# NCKH_2020_Dam.net
KiCad netlist of a schematic drawn in Altium Designer
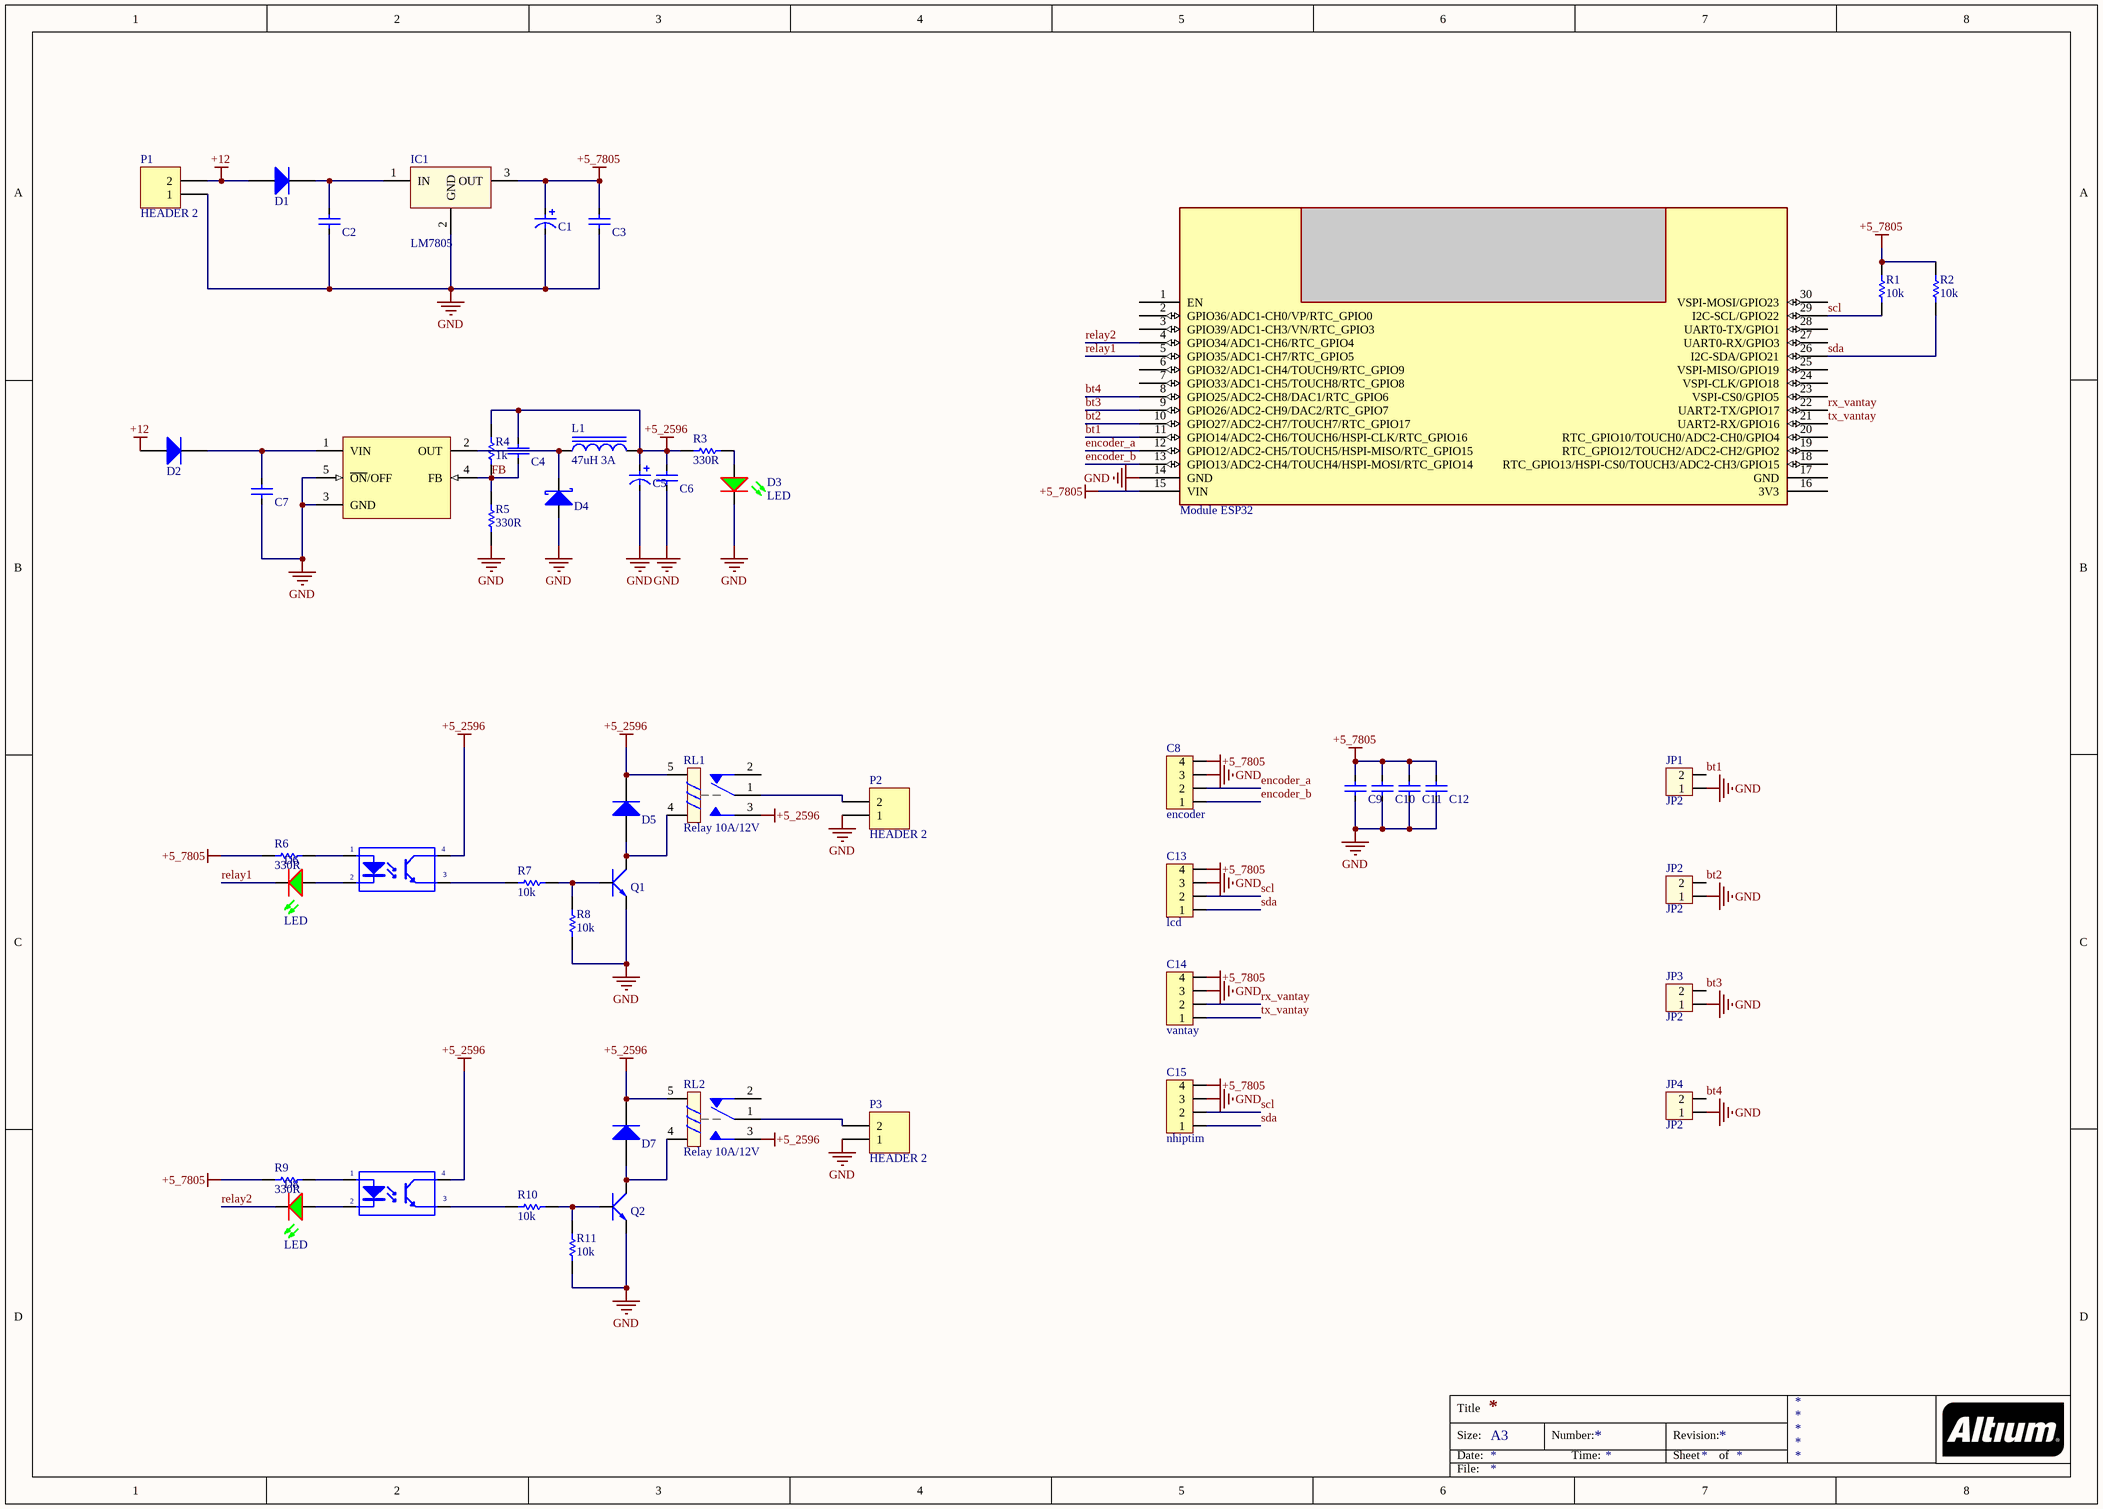
[diagram p0: NCKH 2020_Dam.SchDoc]

(export (version "E")
  (design (tool "Eeschema 10.0.6"))
  (components
    (comp (ref "*1")
      (value "Module ESP32")
      (footprint "Module ESP32")
      (libsource (lib "Lib_NTD_HaUI") (part "Module ESP32"))
    )
    (comp (ref "1") (value "LM2596") (footprint "TO263") (libsource (lib "Lib_NTD_HaUI") (part "LM2596")))
    (comp (ref "C1")
      (value "10uF case A 3216")
      (footprint "CAP TANTALUM A CASE")
      (libsource (lib "Lib_NTD_HaUI") (part "CAP TANTALUM"))
    )
    (comp (ref "C2")
      (value "104")
      (footprint "CAP-0805-SC")
      (libsource (lib "AltiumLibraryTieuBao") (part "CAP-SMDCHIP"))
    )
    (comp (ref "C3")
      (value "104")
      (footprint "CAP-0805-SC")
      (libsource (lib "AltiumLibraryTieuBao") (part "CAP-SMDCHIP"))
    )
    (comp (ref "C4")
      (value "104")
      (footprint "CAP-0805-SC")
      (libsource (lib "AltiumLibraryTieuBao") (part "CAP-SMDCHIP"))
    )
    (comp (ref "C5")
      (value "10uF case A 3216")
      (footprint "CAP TANTALUM A CASE")
      (libsource (lib "Lib_NTD_HaUI") (part "CAP TANTALUM"))
    )
    (comp (ref "C6")
      (value "104")
      (footprint "CAP-0805-SC")
      (libsource (lib "AltiumLibraryTieuBao") (part "CAP-SMDCHIP"))
    )
    (comp (ref "C7")
      (value "104")
      (footprint "CAP-0805-SC")
      (libsource (lib "AltiumLibraryTieuBao") (part "CAP-SMDCHIP"))
    )
    (comp (ref "C8")
      (value "encoder")
      (footprint "Header4")
      (description "Header IDC, 4 x 1 Pin Vertical 2.54mm Pitch (Non-Boxed, Male)")
      (fields
        (field (name "MANUFACTURER") "Würth Elektronik eiSos GmbH")
        (field (name "PARTNO") "613002143121")
        (field (name "CREATED BY") "Karrer Zheng")
      )
      (libsource (lib "LIBRARY") (part "Header4"))
    )
    (comp (ref "C9")
      (value "104")
      (footprint "CAP-0805-SC")
      (libsource (lib "AltiumLibraryTieuBao") (part "CAP-SMDCHIP"))
    )
    (comp (ref "C10")
      (value "104")
      (footprint "CAP-0805-SC")
      (libsource (lib "AltiumLibraryTieuBao") (part "CAP-SMDCHIP"))
    )
    (comp (ref "C11")
      (value "104")
      (footprint "CAP-0805-SC")
      (libsource (lib "AltiumLibraryTieuBao") (part "CAP-SMDCHIP"))
    )
    (comp (ref "C12")
      (value "104")
      (footprint "CAP-0805-SC")
      (libsource (lib "AltiumLibraryTieuBao") (part "CAP-SMDCHIP"))
    )
    (comp (ref "C13")
      (value "lcd")
      (footprint "Header4")
      (description "Header IDC, 4 x 1 Pin Vertical 2.54mm Pitch (Non-Boxed, Male)")
      (fields
        (field (name "MANUFACTURER") "Würth Elektronik eiSos GmbH")
        (field (name "PARTNO") "613002143121")
        (field (name "CREATED BY") "Karrer Zheng")
      )
      (libsource (lib "LIBRARY") (part "Header4"))
    )
    (comp (ref "C14")
      (value "vantay")
      (footprint "Header4")
      (description "Header IDC, 4 x 1 Pin Vertical 2.54mm Pitch (Non-Boxed, Male)")
      (fields
        (field (name "MANUFACTURER") "Würth Elektronik eiSos GmbH")
        (field (name "PARTNO") "613002143121")
        (field (name "CREATED BY") "Karrer Zheng")
      )
      (libsource (lib "LIBRARY") (part "Header4"))
    )
    (comp (ref "C15")
      (value "nhiptim")
      (footprint "Header4")
      (description "Header IDC, 4 x 1 Pin Vertical 2.54mm Pitch (Non-Boxed, Male)")
      (fields
        (field (name "MANUFACTURER") "Würth Elektronik eiSos GmbH")
        (field (name "PARTNO") "613002143121")
        (field (name "CREATED BY") "Karrer Zheng")
      )
      (libsource (lib "LIBRARY") (part "Header4"))
    )
    (comp (ref "D1") (value "M4") (footprint "DO 214AC") (libsource (lib "Lib_NTD_HaUI") (part "DIODE")))
    (comp (ref "D2") (value "M4") (footprint "DO 214AC") (libsource (lib "Lib_NTD_HaUI") (part "DIODE")))
    (comp (ref "D3")
      (value "LED")
      (footprint "LED_SMD_0805")
      (libsource (lib "AltiumLibraryTieuBao") (part "LED"))
    )
    (comp (ref "D4")
      (value "SS34")
      (footprint "DO 214AC")
      (libsource (lib "AltiumLibraryTieuBao") (part "DIODE SCHOTTKY"))
    )
    (comp (ref "D5") (value "M4") (footprint "DO 214AC") (libsource (lib "Lib_NTD_HaUI") (part "DIODE")))
    (comp (ref "D6")
      (value "LED")
      (footprint "LED_SMD_0805")
      (libsource (lib "AltiumLibraryTieuBao") (part "LED"))
    )
    (comp (ref "D7") (value "M4") (footprint "DO 214AC") (libsource (lib "Lib_NTD_HaUI") (part "DIODE")))
    (comp (ref "D8")
      (value "LED")
      (footprint "LED_SMD_0805")
      (libsource (lib "AltiumLibraryTieuBao") (part "LED"))
    )
    (comp (ref "IC1")
      (value "LM7805")
      (footprint "QTO-220H3")
      (description "On ap +, from + 5 to + 24VDC")
      (libsource (lib "syhaunguyen") (part "LM78xx"))
    )
    (comp (ref "JP1")
      (value "JP2")
      (footprint "CON2")
      (description "Connector 2")
      (libsource (lib "syhaunguyen") (part "Con2"))
    )
    (comp (ref "JP2")
      (value "JP2")
      (footprint "CON2")
      (description "Connector 2")
      (libsource (lib "syhaunguyen") (part "Con2"))
    )
    (comp (ref "JP3")
      (value "JP2")
      (footprint "CON2")
      (description "Connector 2")
      (libsource (lib "syhaunguyen") (part "Con2"))
    )
    (comp (ref "JP4")
      (value "JP2")
      (footprint "CON2")
      (description "Connector 2")
      (libsource (lib "syhaunguyen") (part "Con2"))
    )
    (comp (ref "L1")
      (value "47uH 3A")
      (footprint "INDUCTOR SMD 3A")
      (libsource (lib "AltiumLibraryTieuBao") (part "INDUCTOR"))
    )
    (comp (ref "P1")
      (value "HEADER 2")
      (footprint "KF7.62")
      (libsource (lib "AltiumLibraryTieuBao") (part "HEADER 2"))
    )
    (comp (ref "P2") (value "HEADER 2") (footprint "KF7.62") (libsource (lib "") (part "HEADER 2_1")))
    (comp (ref "P3") (value "HEADER 2") (footprint "KF7.62") (libsource (lib "") (part "HEADER 2_1")))
    (comp (ref "Q1") (value "C1815") (footprint "SOT23") (libsource (lib "Lib_NTD_HaUI") (part "C1815")))
    (comp (ref "Q2") (value "C1815") (footprint "SOT23") (libsource (lib "Lib_NTD_HaUI") (part "C1815")))
    (comp (ref "R1")
      (value "10k")
      (footprint "RES-0805-SC")
      (libsource (lib "AltiumLibraryTieuBao") (part "RES"))
    )
    (comp (ref "R2")
      (value "10k")
      (footprint "RES-0805-SC")
      (libsource (lib "AltiumLibraryTieuBao") (part "RES"))
    )
    (comp (ref "R3")
      (value "330R")
      (footprint "RES-0805-SC")
      (libsource (lib "AltiumLibraryTieuBao") (part "RES"))
    )
    (comp (ref "R4")
      (value "1k")
      (footprint "RES-0805-SC")
      (libsource (lib "AltiumLibraryTieuBao") (part "RES"))
    )
    (comp (ref "R5")
      (value "330R")
      (footprint "RES-0805-SC")
      (libsource (lib "AltiumLibraryTieuBao") (part "RES"))
    )
    (comp (ref "R6")
      (value "330R")
      (footprint "RES-0805-SC")
      (libsource (lib "AltiumLibraryTieuBao") (part "RES"))
    )
    (comp (ref "R7")
      (value "10k")
      (footprint "RES-0805-SC")
      (libsource (lib "AltiumLibraryTieuBao") (part "RES"))
    )
    (comp (ref "R8")
      (value "10k")
      (footprint "RES-0805-SC")
      (libsource (lib "AltiumLibraryTieuBao") (part "RES"))
    )
    (comp (ref "R9")
      (value "330R")
      (footprint "RES-0805-SC")
      (libsource (lib "AltiumLibraryTieuBao") (part "RES"))
    )
    (comp (ref "R10")
      (value "10k")
      (footprint "RES-0805-SC")
      (libsource (lib "AltiumLibraryTieuBao") (part "RES"))
    )
    (comp (ref "R11")
      (value "10k")
      (footprint "RES-0805-SC")
      (libsource (lib "AltiumLibraryTieuBao") (part "RES"))
    )
    (comp (ref "RL1")
      (value "Relay 10A/12V")
      (footprint "RL_SPDT_10A")
      (description "Relay SPDT,10A - 12VDC 5 Pin")
      (libsource (lib "syhaunguyen") (part "Relay 1"))
    )
    (comp (ref "RL2")
      (value "Relay 10A/12V")
      (footprint "RL_SPDT_10A")
      (description "Relay SPDT,10A - 12VDC 5 Pin")
      (libsource (lib "syhaunguyen") (part "Relay 1"))
    )
    (comp (ref "U1") (value "PC817") (footprint "PC817") (libsource (lib "Lib_NTD_HaUI") (part "PC817")))
    (comp (ref "U2") (value "PC817") (footprint "PC817") (libsource (lib "Lib_NTD_HaUI") (part "PC817")))
  )
  (nets
    (net (code "1") (name "+5_2596") (class "Default")
      (node (ref "C4") (pin "1") (pinfunction "1_1") (pintype "passive"))
      (node (ref "C5") (pin "1") (pinfunction "1_1") (pintype "passive"))
      (node (ref "C6") (pin "1") (pinfunction "1_1") (pintype "passive"))
      (node (ref "D5") (pin "2") (pinfunction "K_2") (pintype "passive"))
      (node (ref "D7") (pin "2") (pinfunction "K_2") (pintype "passive"))
      (node (ref "L1") (pin "2") (pinfunction "2_2") (pintype "passive"))
      (node (ref "R3") (pin "2") (pinfunction "2_2") (pintype "passive"))
      (node (ref "R4") (pin "2") (pinfunction "2_2") (pintype "passive"))
      (node (ref "RL1") (pin "3") (pinfunction "3_3") (pintype "passive"))
      (node (ref "RL1") (pin "5") (pinfunction "5_5") (pintype "passive"))
      (node (ref "RL2") (pin "3") (pinfunction "3_3") (pintype "passive"))
      (node (ref "RL2") (pin "5") (pinfunction "5_5") (pintype "passive"))
      (node (ref "U1") (pin "4") (pinfunction "C_4") (pintype "passive"))
      (node (ref "U2") (pin "4") (pinfunction "C_4") (pintype "passive"))
    )
    (net (code "2") (name "+5_7805") (class "Default")
      (node (ref "*1") (pin "15") (pinfunction "VIN_15") (pintype "power_in"))
      (node (ref "C1") (pin "1") (pinfunction "1_1") (pintype "passive"))
      (node (ref "C10") (pin "1") (pinfunction "1_1") (pintype "passive"))
      (node (ref "C11") (pin "1") (pinfunction "1_1") (pintype "passive"))
      (node (ref "C12") (pin "1") (pinfunction "1_1") (pintype "passive"))
      (node (ref "C13") (pin "4") (pinfunction "4_4") (pintype "passive"))
      (node (ref "C14") (pin "4") (pinfunction "4_4") (pintype "passive"))
      (node (ref "C15") (pin "4") (pinfunction "4_4") (pintype "passive"))
      (node (ref "C3") (pin "1") (pinfunction "1_1") (pintype "passive"))
      (node (ref "C8") (pin "4") (pinfunction "4_4") (pintype "passive"))
      (node (ref "C9") (pin "1") (pinfunction "1_1") (pintype "passive"))
      (node (ref "IC1") (pin "3") (pinfunction "OUT_3") (pintype "passive"))
      (node (ref "R1") (pin "2") (pinfunction "2_2") (pintype "passive"))
      (node (ref "R2") (pin "2") (pinfunction "2_2") (pintype "passive"))
      (node (ref "R6") (pin "2") (pinfunction "2_2") (pintype "passive"))
      (node (ref "R9") (pin "2") (pinfunction "2_2") (pintype "passive"))
    )
    (net (code "3") (name "+12") (class "Default")
      (node (ref "D1") (pin "1") (pinfunction "A_1") (pintype "passive"))
      (node (ref "D2") (pin "1") (pinfunction "A_1") (pintype "passive"))
      (node (ref "P1") (pin "2") (pinfunction "2_2") (pintype "passive"))
    )
    (net (code "4") (name "/FB") (class "Default")
      (node (ref "1") (pin "4") (pinfunction "FB_4") (pintype "input"))
      (node (ref "C4") (pin "2") (pinfunction "2_2") (pintype "passive"))
      (node (ref "R4") (pin "1") (pinfunction "1_1") (pintype "passive"))
      (node (ref "R5") (pin "2") (pinfunction "2_2") (pintype "passive"))
    )
    (net (code "5") (name "/bt1") (class "Default")
      (node (ref "*1") (pin "11") (pinfunction "GPIO14/ADC2-CH6/TOUCH6/HSPI-CLK/RTC_GPIO16_11") (pintype "bidirectional"))
      (node (ref "JP1") (pin "2") (pinfunction "2_2") (pintype "passive"))
    )
    (net (code "6") (name "/bt2") (class "Default")
      (node (ref "*1") (pin "10") (pinfunction "GPIO27/ADC2-CH7/TOUCH7/RTC_GPIO17_10") (pintype "bidirectional"))
      (node (ref "JP2") (pin "2") (pinfunction "2_2") (pintype "passive"))
    )
    (net (code "7") (name "/bt3") (class "Default")
      (node (ref "*1") (pin "9") (pinfunction "GPIO26/ADC2-CH9/DAC2/RTC_GPIO7_9") (pintype "bidirectional"))
      (node (ref "JP3") (pin "2") (pinfunction "2_2") (pintype "passive"))
    )
    (net (code "8") (name "/bt4") (class "Default")
      (node (ref "*1") (pin "8") (pinfunction "GPIO25/ADC2-CH8/DAC1/RTC_GPIO6_8") (pintype "bidirectional"))
      (node (ref "JP4") (pin "2") (pinfunction "2_2") (pintype "passive"))
    )
    (net (code "9") (name "/encoder_a") (class "Default")
      (node (ref "*1") (pin "12") (pinfunction "GPIO12/ADC2-CH5/TOUCH5/HSPI-MISO/RTC_GPIO15_12") (pintype "bidirectional"))
      (node (ref "C8") (pin "2") (pinfunction "2_2") (pintype "passive"))
    )
    (net (code "10") (name "/encoder_b") (class "Default")
      (node (ref "*1") (pin "13") (pinfunction "GPIO13/ADC2-CH4/TOUCH4/HSPI-MOSI/RTC_GPIO14_13") (pintype "bidirectional"))
      (node (ref "C8") (pin "1") (pinfunction "1_1") (pintype "passive"))
    )
    (net (code "11") (name "/relay1") (class "Default")
      (node (ref "*1") (pin "5") (pinfunction "GPIO35/ADC1-CH7/RTC_GPIO5_5") (pintype "bidirectional"))
      (node (ref "D6") (pin "2") (pinfunction "K_2") (pintype "passive"))
    )
    (net (code "12") (name "/relay2") (class "Default")
      (node (ref "*1") (pin "4") (pinfunction "GPIO34/ADC1-CH6/RTC_GPIO4_4") (pintype "bidirectional"))
      (node (ref "D8") (pin "2") (pinfunction "K_2") (pintype "passive"))
    )
    (net (code "13") (name "/rx_vantay") (class "Default")
      (node (ref "*1") (pin "22") (pinfunction "UART2-TX/GPIO17_22") (pintype "bidirectional"))
      (node (ref "C14") (pin "2") (pinfunction "2_2") (pintype "passive"))
    )
    (net (code "14") (name "/scl") (class "Default")
      (node (ref "*1") (pin "29") (pinfunction "I2C-SCL/GPIO22_29") (pintype "bidirectional"))
      (node (ref "C13") (pin "2") (pinfunction "2_2") (pintype "passive"))
      (node (ref "C15") (pin "2") (pinfunction "2_2") (pintype "passive"))
      (node (ref "R1") (pin "1") (pinfunction "1_1") (pintype "passive"))
    )
    (net (code "15") (name "/sda") (class "Default")
      (node (ref "*1") (pin "26") (pinfunction "I2C-SDA/GPIO21_26") (pintype "bidirectional"))
      (node (ref "C13") (pin "1") (pinfunction "1_1") (pintype "passive"))
      (node (ref "C15") (pin "1") (pinfunction "1_1") (pintype "passive"))
      (node (ref "R2") (pin "1") (pinfunction "1_1") (pintype "passive"))
    )
    (net (code "16") (name "/tx_vantay") (class "Default")
      (node (ref "*1") (pin "21") (pinfunction "UART2-RX/GPIO16_21") (pintype "bidirectional"))
      (node (ref "C14") (pin "1") (pinfunction "1_1") (pintype "passive"))
    )
    (net (code "17") (name "GND") (class "Default")
      (node (ref "*1") (pin "14") (pinfunction "GND_14") (pintype "power_in"))
      (node (ref "1") (pin "3") (pinfunction "GND_3") (pintype "power_in"))
      (node (ref "1") (pin "5") (pinfunction "~{ON}/OFF_5") (pintype "input"))
      (node (ref "C1") (pin "2") (pinfunction "2_2") (pintype "passive"))
      (node (ref "C10") (pin "2") (pinfunction "2_2") (pintype "passive"))
      (node (ref "C11") (pin "2") (pinfunction "2_2") (pintype "passive"))
      (node (ref "C12") (pin "2") (pinfunction "2_2") (pintype "passive"))
      (node (ref "C13") (pin "3") (pinfunction "3_3") (pintype "passive"))
      (node (ref "C14") (pin "3") (pinfunction "3_3") (pintype "passive"))
      (node (ref "C15") (pin "3") (pinfunction "3_3") (pintype "passive"))
      (node (ref "C2") (pin "2") (pinfunction "2_2") (pintype "passive"))
      (node (ref "C3") (pin "2") (pinfunction "2_2") (pintype "passive"))
      (node (ref "C5") (pin "2") (pinfunction "2_2") (pintype "passive"))
      (node (ref "C6") (pin "2") (pinfunction "2_2") (pintype "passive"))
      (node (ref "C7") (pin "2") (pinfunction "2_2") (pintype "passive"))
      (node (ref "C8") (pin "3") (pinfunction "3_3") (pintype "passive"))
      (node (ref "C9") (pin "2") (pinfunction "2_2") (pintype "passive"))
      (node (ref "D3") (pin "2") (pinfunction "K_2") (pintype "passive"))
      (node (ref "D4") (pin "1") (pinfunction "A_1") (pintype "passive"))
      (node (ref "IC1") (pin "2") (pinfunction "GND_2") (pintype "passive"))
      (node (ref "JP1") (pin "1") (pinfunction "1_1") (pintype "passive"))
      (node (ref "JP2") (pin "1") (pinfunction "1_1") (pintype "passive"))
      (node (ref "JP3") (pin "1") (pinfunction "1_1") (pintype "passive"))
      (node (ref "JP4") (pin "1") (pinfunction "1_1") (pintype "passive"))
      (node (ref "P1") (pin "1") (pinfunction "1_1") (pintype "passive"))
      (node (ref "P2") (pin "1") (pinfunction "1_1") (pintype "passive"))
      (node (ref "P3") (pin "1") (pinfunction "1_1") (pintype "passive"))
      (node (ref "Q1") (pin "2") (pinfunction "E_2") (pintype "passive"))
      (node (ref "Q2") (pin "2") (pinfunction "E_2") (pintype "passive"))
      (node (ref "R11") (pin "1") (pinfunction "1_1") (pintype "passive"))
      (node (ref "R5") (pin "1") (pinfunction "1_1") (pintype "passive"))
      (node (ref "R8") (pin "1") (pinfunction "1_1") (pintype "passive"))
    )
    (net (code "18") (name "Net-(1-OUT)") (class "Default")
      (node (ref "1") (pin "2") (pinfunction "OUT_2") (pintype "power_in"))
      (node (ref "D4") (pin "2") (pinfunction "K_2") (pintype "passive"))
      (node (ref "L1") (pin "1") (pinfunction "1_1") (pintype "passive"))
    )
    (net (code "19") (name "Net-(1-VIN)") (class "Default")
      (node (ref "1") (pin "1") (pinfunction "VIN_1") (pintype "power_in"))
      (node (ref "C7") (pin "1") (pinfunction "1_1") (pintype "passive"))
      (node (ref "D2") (pin "2") (pinfunction "K_2") (pintype "passive"))
    )
    (net (code "20") (name "Net-(D1-K)") (class "Default")
      (node (ref "C2") (pin "1") (pinfunction "1_1") (pintype "passive"))
      (node (ref "D1") (pin "2") (pinfunction "K_2") (pintype "passive"))
      (node (ref "IC1") (pin "1") (pinfunction "IN_1") (pintype "passive"))
    )
    (net (code "21") (name "Net-(D3-A)") (class "Default")
      (node (ref "D3") (pin "1") (pinfunction "A_1") (pintype "passive"))
      (node (ref "R3") (pin "1") (pinfunction "1_1") (pintype "passive"))
    )
    (net (code "22") (name "Net-(D5-A)") (class "Default")
      (node (ref "D5") (pin "1") (pinfunction "A_1") (pintype "passive"))
      (node (ref "Q1") (pin "3") (pinfunction "C_3") (pintype "passive"))
      (node (ref "RL1") (pin "4") (pinfunction "4_4") (pintype "passive"))
    )
    (net (code "23") (name "Net-(D6-A)") (class "Default")
      (node (ref "D6") (pin "1") (pinfunction "A_1") (pintype "passive"))
      (node (ref "U1") (pin "2") (pinfunction "K_2") (pintype "passive"))
    )
    (net (code "24") (name "Net-(D7-A)") (class "Default")
      (node (ref "D7") (pin "1") (pinfunction "A_1") (pintype "passive"))
      (node (ref "Q2") (pin "3") (pinfunction "C_3") (pintype "passive"))
      (node (ref "RL2") (pin "4") (pinfunction "4_4") (pintype "passive"))
    )
    (net (code "25") (name "Net-(D8-A)") (class "Default")
      (node (ref "D8") (pin "1") (pinfunction "A_1") (pintype "passive"))
      (node (ref "U2") (pin "2") (pinfunction "K_2") (pintype "passive"))
    )
    (net (code "26") (name "Net-(P2-Pad2)") (class "Default")
      (node (ref "P2") (pin "2") (pinfunction "2_2") (pintype "passive"))
      (node (ref "RL1") (pin "1") (pinfunction "1_1") (pintype "passive"))
    )
    (net (code "27") (name "Net-(P3-Pad2)") (class "Default")
      (node (ref "P3") (pin "2") (pinfunction "2_2") (pintype "passive"))
      (node (ref "RL2") (pin "1") (pinfunction "1_1") (pintype "passive"))
    )
    (net (code "28") (name "Net-(Q1-B)") (class "Default")
      (node (ref "Q1") (pin "1") (pinfunction "B_1") (pintype "passive"))
      (node (ref "R7") (pin "1") (pinfunction "1_1") (pintype "passive"))
      (node (ref "R8") (pin "2") (pinfunction "2_2") (pintype "passive"))
    )
    (net (code "29") (name "Net-(Q2-B)") (class "Default")
      (node (ref "Q2") (pin "1") (pinfunction "B_1") (pintype "passive"))
      (node (ref "R10") (pin "1") (pinfunction "1_1") (pintype "passive"))
      (node (ref "R11") (pin "2") (pinfunction "2_2") (pintype "passive"))
    )
    (net (code "30") (name "Net-(U1-A)") (class "Default")
      (node (ref "R6") (pin "1") (pinfunction "1_1") (pintype "passive"))
      (node (ref "U1") (pin "1") (pinfunction "A_1") (pintype "passive"))
    )
    (net (code "31") (name "Net-(U1-E)") (class "Default")
      (node (ref "R7") (pin "2") (pinfunction "2_2") (pintype "passive"))
      (node (ref "U1") (pin "3") (pinfunction "E_3") (pintype "passive"))
    )
    (net (code "32") (name "Net-(U2-A)") (class "Default")
      (node (ref "R9") (pin "1") (pinfunction "1_1") (pintype "passive"))
      (node (ref "U2") (pin "1") (pinfunction "A_1") (pintype "passive"))
    )
    (net (code "33") (name "Net-(U2-E)") (class "Default")
      (node (ref "R10") (pin "2") (pinfunction "2_2") (pintype "passive"))
      (node (ref "U2") (pin "3") (pinfunction "E_3") (pintype "passive"))
    )
    (net (code "34") (name "unconnected-(*1-3V3-Pad16)") (class "Default")
      (node (ref "*1") (pin "16") (pinfunction "3V3_16") (pintype "power_in"))
    )
    (net (code "35") (name "unconnected-(*1-EN-Pad1)") (class "Default")
      (node (ref "*1") (pin "1") (pinfunction "EN_1") (pintype "passive"))
    )
    (net (code "36") (name "unconnected-(*1-GND-Pad17)") (class "Default")
      (node (ref "*1") (pin "17") (pinfunction "GND_17") (pintype "power_in"))
    )
    (net (code "37") (name "unconnected-(*1-GPIO32{slash}ADC1-CH4{slash}TOUCH9{slash}RTC_GPIO9-Pad6)") (class "Default")
      (node (ref "*1") (pin "6") (pinfunction "GPIO32/ADC1-CH4/TOUCH9/RTC_GPIO9_6") (pintype "bidirectional"))
    )
    (net (code "38") (name "unconnected-(*1-GPIO33{slash}ADC1-CH5{slash}TOUCH8{slash}RTC_GPIO8-Pad7)") (class "Default")
      (node (ref "*1") (pin "7") (pinfunction "GPIO33/ADC1-CH5/TOUCH8/RTC_GPIO8_7") (pintype "bidirectional"))
    )
    (net (code "39") (name "unconnected-(*1-GPIO36{slash}ADC1-CH0{slash}VP{slash}RTC_GPIO0-Pad2)") (class "Default")
      (node (ref "*1") (pin "2") (pinfunction "GPIO36/ADC1-CH0/VP/RTC_GPIO0_2") (pintype "bidirectional"))
    )
    (net (code "40") (name "unconnected-(*1-GPIO39{slash}ADC1-CH3{slash}VN{slash}RTC_GPIO3-Pad3)") (class "Default")
      (node (ref "*1") (pin "3") (pinfunction "GPIO39/ADC1-CH3/VN/RTC_GPIO3_3") (pintype "bidirectional"))
    )
    (net (code "41") (name "unconnected-(*1-RTC_GPIO10{slash}TOUCH0{slash}ADC2-CH0{slash}GPIO4-Pad20)") (class "Default")
      (node (ref "*1") (pin "20") (pinfunction "RTC_GPIO10/TOUCH0/ADC2-CH0/GPIO4_20") (pintype "bidirectional"))
    )
    (net (code "42") (name "unconnected-(*1-RTC_GPIO12{slash}TOUCH2{slash}ADC2-CH2{slash}GPIO2-Pad19)") (class "Default")
      (node (ref "*1") (pin "19") (pinfunction "RTC_GPIO12/TOUCH2/ADC2-CH2/GPIO2_19") (pintype "bidirectional"))
    )
    (net (code "43") (name "unconnected-(*1-RTC_GPIO13{slash}HSPI-CS0{slash}TOUCH3{slash}ADC2-CH3{slash}GPIO15-Pad18)") (class "Default")
      (node (ref "*1") (pin "18") (pinfunction "RTC_GPIO13/HSPI-CS0/TOUCH3/ADC2-CH3/GPIO15_18") (pintype "bidirectional"))
    )
    (net (code "44") (name "unconnected-(*1-UART0-RX{slash}GPIO3-Pad27)") (class "Default")
      (node (ref "*1") (pin "27") (pinfunction "UART0-RX/GPIO3_27") (pintype "bidirectional"))
    )
    (net (code "45") (name "unconnected-(*1-UART0-TX{slash}GPIO1-Pad28)") (class "Default")
      (node (ref "*1") (pin "28") (pinfunction "UART0-TX/GPIO1_28") (pintype "bidirectional"))
    )
    (net (code "46") (name "unconnected-(*1-VSPI-CLK{slash}GPIO18-Pad24)") (class "Default")
      (node (ref "*1") (pin "24") (pinfunction "VSPI-CLK/GPIO18_24") (pintype "bidirectional"))
    )
    (net (code "47") (name "unconnected-(*1-VSPI-CS0{slash}GPIO5-Pad23)") (class "Default")
      (node (ref "*1") (pin "23") (pinfunction "VSPI-CS0/GPIO5_23") (pintype "bidirectional"))
    )
    (net (code "48") (name "unconnected-(*1-VSPI-MISO{slash}GPIO19-Pad25)") (class "Default")
      (node (ref "*1") (pin "25") (pinfunction "VSPI-MISO/GPIO19_25") (pintype "bidirectional"))
    )
    (net (code "49") (name "unconnected-(*1-VSPI-MOSI{slash}GPIO23-Pad30)") (class "Default")
      (node (ref "*1") (pin "30") (pinfunction "VSPI-MOSI/GPIO23_30") (pintype "bidirectional"))
    )
    (net (code "50") (name "unconnected-(RL1-Pad2)") (class "Default")
      (node (ref "RL1") (pin "2") (pinfunction "2_2") (pintype "passive"))
    )
    (net (code "51") (name "unconnected-(RL2-Pad2)") (class "Default")
      (node (ref "RL2") (pin "2") (pinfunction "2_2") (pintype "passive"))
    )
  )
)
